# cpu_pwr.net
KiCad netlist of a schematic drawn in Altium Designer
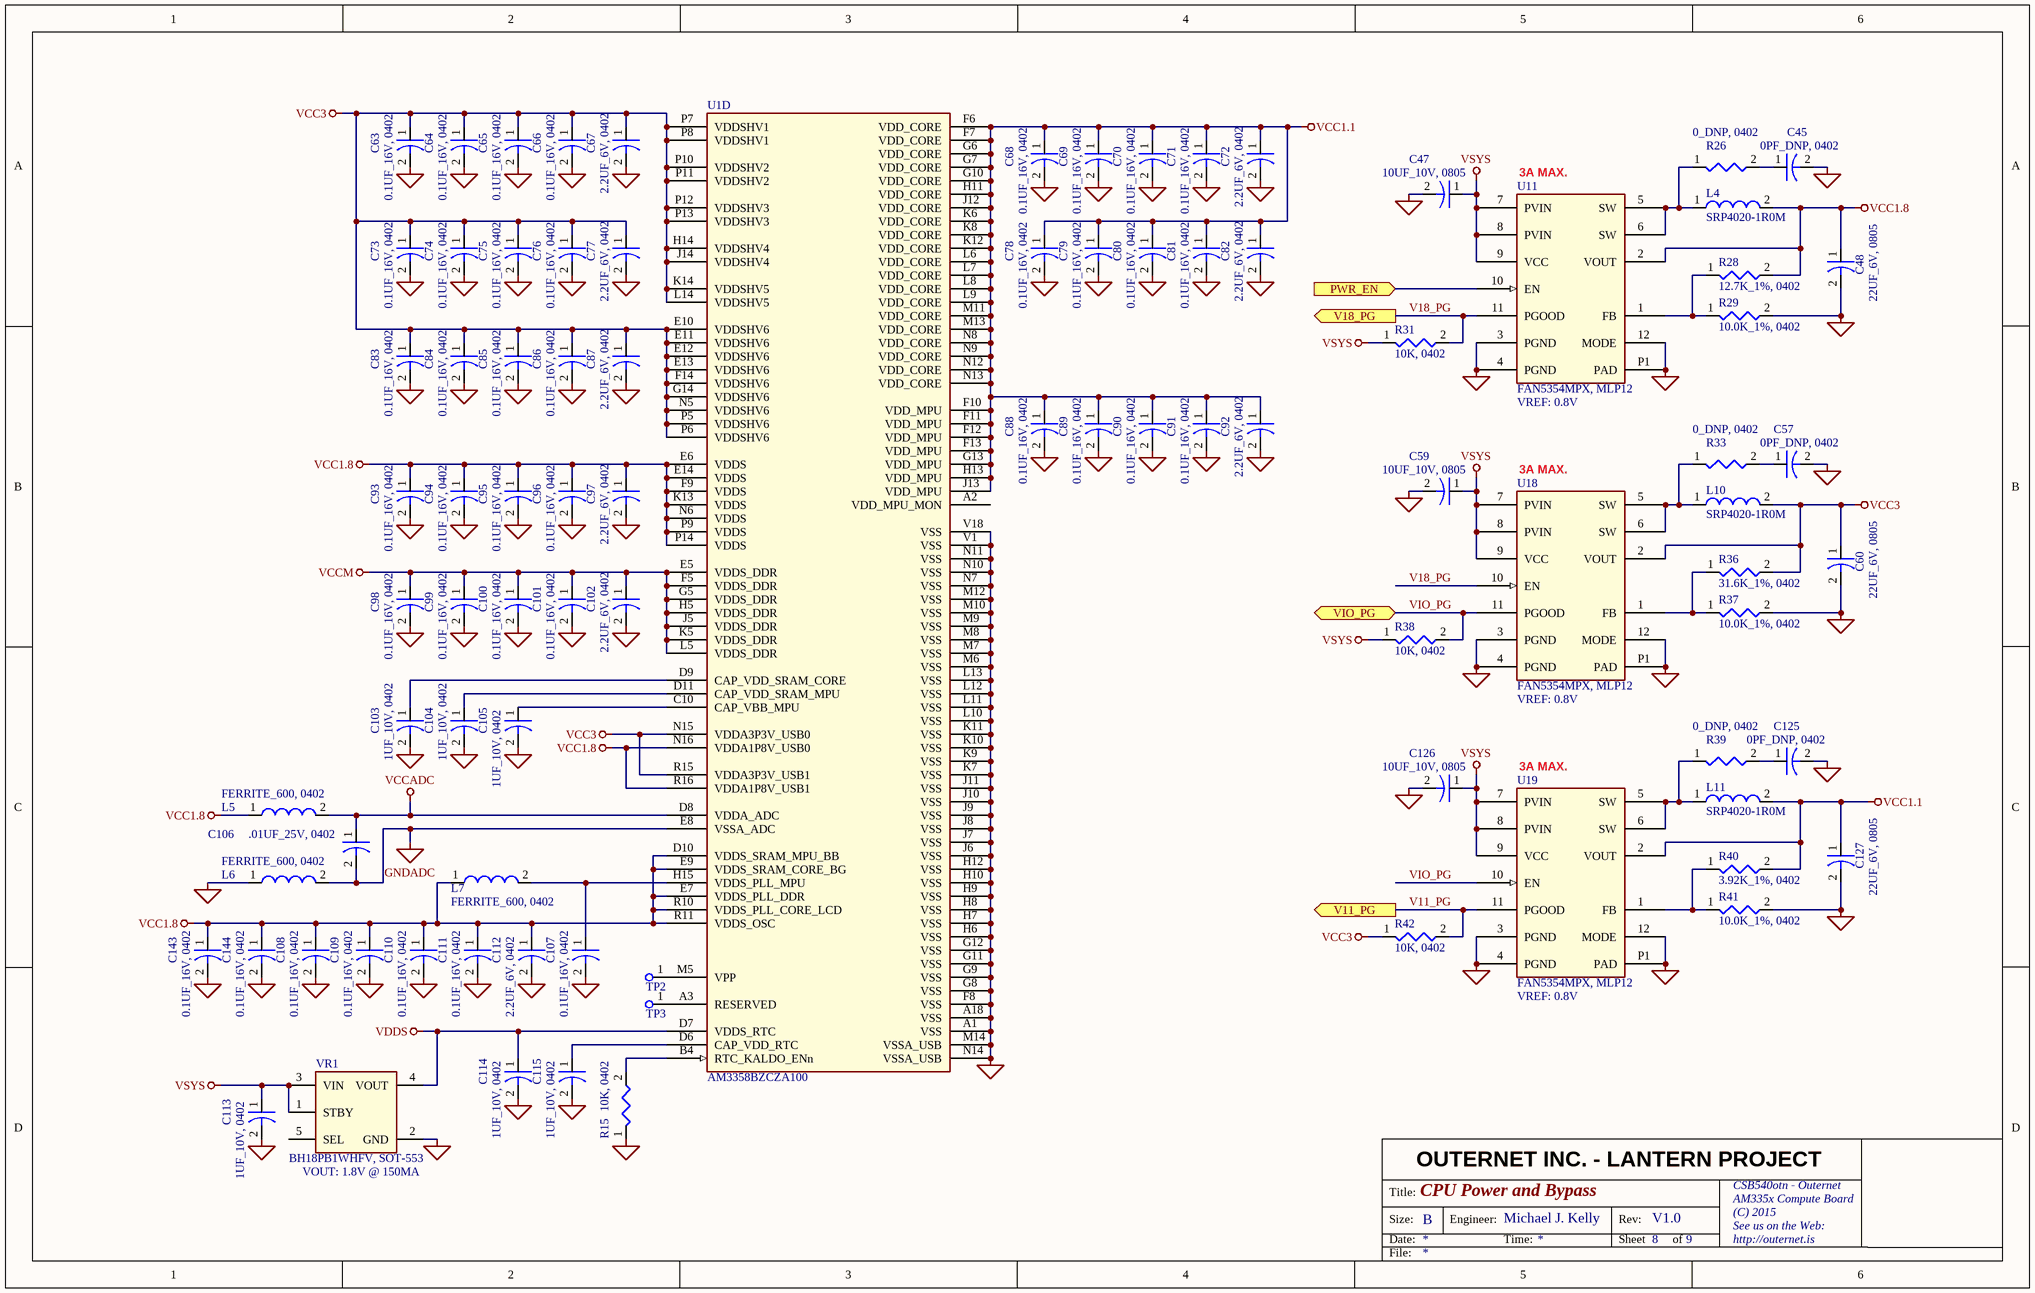
[diagram p0: cpu_pwr.SchDoc]

(export (version "E")
  (design (tool "Eeschema 10.0.6"))
  (components
    (comp (ref "C45")
      (value "0PF_DNP, 0402")
      (footprint "0402C")
      (description "CAP - 0402 PKG")
      (libsource (lib "COGENT_Library") (part "0PF_DNP, 0402"))
    )
    (comp (ref "C47")
      (value "10UF_10V, 0805")
      (footprint "0805C")
      (description "CAP - 0805 PKG")
      (libsource (lib "COGENT_Library") (part "10UF_10V, 0805"))
    )
    (comp (ref "C48")
      (value "22UF_6V, 0805")
      (footprint "0805C")
      (description "CAP - 0805 PKG")
      (libsource (lib "COGENT_Library") (part "22UF_6V, 0805"))
    )
    (comp (ref "C57")
      (value "0PF_DNP, 0402")
      (footprint "0402C")
      (description "CAP - 0402 PKG")
      (libsource (lib "COGENT_Library") (part "0PF_DNP, 0402"))
    )
    (comp (ref "C59")
      (value "10UF_10V, 0805")
      (footprint "0805C")
      (description "CAP - 0805 PKG")
      (libsource (lib "COGENT_Library") (part "10UF_10V, 0805"))
    )
    (comp (ref "C60")
      (value "22UF_6V, 0805")
      (footprint "0805C")
      (description "CAP - 0805 PKG")
      (libsource (lib "COGENT_Library") (part "22UF_6V, 0805"))
    )
    (comp (ref "C63")
      (value "0.1UF_16V, 0402")
      (footprint "0402C")
      (description "CAP - 0402 PKG")
      (libsource (lib "COGENT_Library") (part "0.1UF_16V, 0402"))
    )
    (comp (ref "C64")
      (value "0.1UF_16V, 0402")
      (footprint "0402C")
      (description "CAP - 0402 PKG")
      (libsource (lib "COGENT_Library") (part "0.1UF_16V, 0402"))
    )
    (comp (ref "C65")
      (value "0.1UF_16V, 0402")
      (footprint "0402C")
      (description "CAP - 0402 PKG")
      (libsource (lib "COGENT_Library") (part "0.1UF_16V, 0402"))
    )
    (comp (ref "C66")
      (value "0.1UF_16V, 0402")
      (footprint "0402C")
      (description "CAP - 0402 PKG")
      (libsource (lib "COGENT_Library") (part "0.1UF_16V, 0402"))
    )
    (comp (ref "C67")
      (value "2.2UF_6V, 0402")
      (footprint "0402C")
      (description "CAP - 0402 PKG")
      (libsource (lib "COGENT_Library") (part "2.2UF_6V, 0402"))
    )
    (comp (ref "C68")
      (value "0.1UF_16V, 0402")
      (footprint "0402C")
      (description "CAP - 0402 PKG")
      (libsource (lib "COGENT_Library") (part "0.1UF_16V, 0402"))
    )
    (comp (ref "C69")
      (value "0.1UF_16V, 0402")
      (footprint "0402C")
      (description "CAP - 0402 PKG")
      (libsource (lib "COGENT_Library") (part "0.1UF_16V, 0402"))
    )
    (comp (ref "C70")
      (value "0.1UF_16V, 0402")
      (footprint "0402C")
      (description "CAP - 0402 PKG")
      (libsource (lib "COGENT_Library") (part "0.1UF_16V, 0402"))
    )
    (comp (ref "C71")
      (value "0.1UF_16V, 0402")
      (footprint "0402C")
      (description "CAP - 0402 PKG")
      (libsource (lib "COGENT_Library") (part "0.1UF_16V, 0402"))
    )
    (comp (ref "C72")
      (value "2.2UF_6V, 0402")
      (footprint "0402C")
      (description "CAP - 0402 PKG")
      (libsource (lib "COGENT_Library") (part "2.2UF_6V, 0402"))
    )
    (comp (ref "C73")
      (value "0.1UF_16V, 0402")
      (footprint "0402C")
      (description "CAP - 0402 PKG")
      (libsource (lib "COGENT_Library") (part "0.1UF_16V, 0402"))
    )
    (comp (ref "C74")
      (value "0.1UF_16V, 0402")
      (footprint "0402C")
      (description "CAP - 0402 PKG")
      (libsource (lib "COGENT_Library") (part "0.1UF_16V, 0402"))
    )
    (comp (ref "C75")
      (value "0.1UF_16V, 0402")
      (footprint "0402C")
      (description "CAP - 0402 PKG")
      (libsource (lib "COGENT_Library") (part "0.1UF_16V, 0402"))
    )
    (comp (ref "C76")
      (value "0.1UF_16V, 0402")
      (footprint "0402C")
      (description "CAP - 0402 PKG")
      (libsource (lib "COGENT_Library") (part "0.1UF_16V, 0402"))
    )
    (comp (ref "C77")
      (value "2.2UF_6V, 0402")
      (footprint "0402C")
      (description "CAP - 0402 PKG")
      (libsource (lib "COGENT_Library") (part "2.2UF_6V, 0402"))
    )
    (comp (ref "C78")
      (value "0.1UF_16V, 0402")
      (footprint "0402C")
      (description "CAP - 0402 PKG")
      (libsource (lib "COGENT_Library") (part "0.1UF_16V, 0402"))
    )
    (comp (ref "C79")
      (value "0.1UF_16V, 0402")
      (footprint "0402C")
      (description "CAP - 0402 PKG")
      (libsource (lib "COGENT_Library") (part "0.1UF_16V, 0402"))
    )
    (comp (ref "C80")
      (value "0.1UF_16V, 0402")
      (footprint "0402C")
      (description "CAP - 0402 PKG")
      (libsource (lib "COGENT_Library") (part "0.1UF_16V, 0402"))
    )
    (comp (ref "C81")
      (value "0.1UF_16V, 0402")
      (footprint "0402C")
      (description "CAP - 0402 PKG")
      (libsource (lib "COGENT_Library") (part "0.1UF_16V, 0402"))
    )
    (comp (ref "C82")
      (value "2.2UF_6V, 0402")
      (footprint "0402C")
      (description "CAP - 0402 PKG")
      (libsource (lib "COGENT_Library") (part "2.2UF_6V, 0402"))
    )
    (comp (ref "C83")
      (value "0.1UF_16V, 0402")
      (footprint "0402C")
      (description "CAP - 0402 PKG")
      (libsource (lib "COGENT_Library") (part "0.1UF_16V, 0402"))
    )
    (comp (ref "C84")
      (value "0.1UF_16V, 0402")
      (footprint "0402C")
      (description "CAP - 0402 PKG")
      (libsource (lib "COGENT_Library") (part "0.1UF_16V, 0402"))
    )
    (comp (ref "C85")
      (value "0.1UF_16V, 0402")
      (footprint "0402C")
      (description "CAP - 0402 PKG")
      (libsource (lib "COGENT_Library") (part "0.1UF_16V, 0402"))
    )
    (comp (ref "C86")
      (value "0.1UF_16V, 0402")
      (footprint "0402C")
      (description "CAP - 0402 PKG")
      (libsource (lib "COGENT_Library") (part "0.1UF_16V, 0402"))
    )
    (comp (ref "C87")
      (value "2.2UF_6V, 0402")
      (footprint "0402C")
      (description "CAP - 0402 PKG")
      (libsource (lib "COGENT_Library") (part "2.2UF_6V, 0402"))
    )
    (comp (ref "C88")
      (value "0.1UF_16V, 0402")
      (footprint "0402C")
      (description "CAP - 0402 PKG")
      (libsource (lib "COGENT_Library") (part "0.1UF_16V, 0402"))
    )
    (comp (ref "C89")
      (value "0.1UF_16V, 0402")
      (footprint "0402C")
      (description "CAP - 0402 PKG")
      (libsource (lib "COGENT_Library") (part "0.1UF_16V, 0402"))
    )
    (comp (ref "C90")
      (value "0.1UF_16V, 0402")
      (footprint "0402C")
      (description "CAP - 0402 PKG")
      (libsource (lib "COGENT_Library") (part "0.1UF_16V, 0402"))
    )
    (comp (ref "C91")
      (value "0.1UF_16V, 0402")
      (footprint "0402C")
      (description "CAP - 0402 PKG")
      (libsource (lib "COGENT_Library") (part "0.1UF_16V, 0402"))
    )
    (comp (ref "C92")
      (value "2.2UF_6V, 0402")
      (footprint "0402C")
      (description "CAP - 0402 PKG")
      (libsource (lib "COGENT_Library") (part "2.2UF_6V, 0402"))
    )
    (comp (ref "C93")
      (value "0.1UF_16V, 0402")
      (footprint "0402C")
      (description "CAP - 0402 PKG")
      (libsource (lib "COGENT_Library") (part "0.1UF_16V, 0402"))
    )
    (comp (ref "C94")
      (value "0.1UF_16V, 0402")
      (footprint "0402C")
      (description "CAP - 0402 PKG")
      (libsource (lib "COGENT_Library") (part "0.1UF_16V, 0402"))
    )
    (comp (ref "C95")
      (value "0.1UF_16V, 0402")
      (footprint "0402C")
      (description "CAP - 0402 PKG")
      (libsource (lib "COGENT_Library") (part "0.1UF_16V, 0402"))
    )
    (comp (ref "C96")
      (value "0.1UF_16V, 0402")
      (footprint "0402C")
      (description "CAP - 0402 PKG")
      (libsource (lib "COGENT_Library") (part "0.1UF_16V, 0402"))
    )
    (comp (ref "C97")
      (value "2.2UF_6V, 0402")
      (footprint "0402C")
      (description "CAP - 0402 PKG")
      (libsource (lib "COGENT_Library") (part "2.2UF_6V, 0402"))
    )
    (comp (ref "C98")
      (value "0.1UF_16V, 0402")
      (footprint "0402C")
      (description "CAP - 0402 PKG")
      (libsource (lib "COGENT_Library") (part "0.1UF_16V, 0402"))
    )
    (comp (ref "C99")
      (value "0.1UF_16V, 0402")
      (footprint "0402C")
      (description "CAP - 0402 PKG")
      (libsource (lib "COGENT_Library") (part "0.1UF_16V, 0402"))
    )
    (comp (ref "C100")
      (value "0.1UF_16V, 0402")
      (footprint "0402C")
      (description "CAP - 0402 PKG")
      (libsource (lib "COGENT_Library") (part "0.1UF_16V, 0402"))
    )
    (comp (ref "C101")
      (value "0.1UF_16V, 0402")
      (footprint "0402C")
      (description "CAP - 0402 PKG")
      (libsource (lib "COGENT_Library") (part "0.1UF_16V, 0402"))
    )
    (comp (ref "C102")
      (value "2.2UF_6V, 0402")
      (footprint "0402C")
      (description "CAP - 0402 PKG")
      (libsource (lib "COGENT_Library") (part "2.2UF_6V, 0402"))
    )
    (comp (ref "C103")
      (value "1UF_10V, 0402")
      (footprint "0402C")
      (description "CAP - 0402 PKG")
      (libsource (lib "COGENT_Library") (part "1UF_10V, 0402"))
    )
    (comp (ref "C104")
      (value "1UF_10V, 0402")
      (footprint "0402C")
      (description "CAP - 0402 PKG")
      (libsource (lib "COGENT_Library") (part "1UF_10V, 0402"))
    )
    (comp (ref "C105")
      (value "1UF_10V, 0402")
      (footprint "0402C")
      (description "CAP - 0402 PKG")
      (libsource (lib "COGENT_Library") (part "1UF_10V, 0402"))
    )
    (comp (ref "C106")
      (value ".01UF_25V, 0402")
      (footprint "0402C")
      (description "CAP - 0402 PKG")
      (libsource (lib "COGENT_Library") (part ".01UF_25V, 0402"))
    )
    (comp (ref "C107")
      (value "0.1UF_16V, 0402")
      (footprint "0402C")
      (description "CAP - 0402 PKG")
      (libsource (lib "COGENT_Library") (part "0.1UF_16V, 0402"))
    )
    (comp (ref "C108")
      (value "0.1UF_16V, 0402")
      (footprint "0402C")
      (description "CAP - 0402 PKG")
      (libsource (lib "COGENT_Library") (part "0.1UF_16V, 0402"))
    )
    (comp (ref "C109")
      (value "0.1UF_16V, 0402")
      (footprint "0402C")
      (description "CAP - 0402 PKG")
      (libsource (lib "COGENT_Library") (part "0.1UF_16V, 0402"))
    )
    (comp (ref "C110")
      (value "0.1UF_16V, 0402")
      (footprint "0402C")
      (description "CAP - 0402 PKG")
      (libsource (lib "COGENT_Library") (part "0.1UF_16V, 0402"))
    )
    (comp (ref "C111")
      (value "0.1UF_16V, 0402")
      (footprint "0402C")
      (description "CAP - 0402 PKG")
      (libsource (lib "COGENT_Library") (part "0.1UF_16V, 0402"))
    )
    (comp (ref "C112")
      (value "2.2UF_6V, 0402")
      (footprint "0402C")
      (description "CAP - 0402 PKG")
      (libsource (lib "COGENT_Library") (part "2.2UF_6V, 0402"))
    )
    (comp (ref "C113")
      (value "1UF_10V, 0402")
      (footprint "0402C")
      (description "CAP - 0402 PKG")
      (libsource (lib "COGENT_Library") (part "1UF_10V, 0402"))
    )
    (comp (ref "C114")
      (value "1UF_10V, 0402")
      (footprint "0402C")
      (description "CAP - 0402 PKG")
      (libsource (lib "COGENT_Library") (part "1UF_10V, 0402"))
    )
    (comp (ref "C115")
      (value "1UF_10V, 0402")
      (footprint "0402C")
      (description "CAP - 0402 PKG")
      (libsource (lib "COGENT_Library") (part "1UF_10V, 0402"))
    )
    (comp (ref "C125")
      (value "0PF_DNP, 0402")
      (footprint "0402C")
      (description "CAP - 0402 PKG")
      (libsource (lib "COGENT_Library") (part "0PF_DNP, 0402"))
    )
    (comp (ref "C126")
      (value "10UF_10V, 0805")
      (footprint "0805C")
      (description "CAP - 0805 PKG")
      (libsource (lib "COGENT_Library") (part "10UF_10V, 0805"))
    )
    (comp (ref "C127")
      (value "22UF_6V, 0805")
      (footprint "0805C")
      (description "CAP - 0805 PKG")
      (libsource (lib "COGENT_Library") (part "22UF_6V, 0805"))
    )
    (comp (ref "C143")
      (value "0.1UF_16V, 0402")
      (footprint "0402C")
      (description "CAP - 0402 PKG")
      (libsource (lib "COGENT_Library") (part "0.1UF_16V, 0402"))
    )
    (comp (ref "C144")
      (value "0.1UF_16V, 0402")
      (footprint "0402C")
      (description "CAP - 0402 PKG")
      (libsource (lib "COGENT_Library") (part "0.1UF_16V, 0402"))
    )
    (comp (ref "L4")
      (value "SRP4020-1R0M")
      (footprint "SRP4020")
      (description "INDUCTOR - 1.0UH, 5/6A, 4MM x 4MM x 2MM, 22mohm")
      (libsource (lib "COGENT_Library") (part "SRP4020-1R0M"))
    )
    (comp (ref "L5")
      (value "FERRITE_600, 0402")
      (footprint "0402L")
      (description "FERRITE BEAD - 600 OHM, 300MA, 0402 PKG")
      (libsource (lib "COGENT_Library") (part "FERRITE_600, 0402"))
    )
    (comp (ref "L6")
      (value "FERRITE_600, 0402")
      (footprint "0402L")
      (description "FERRITE BEAD - 600 OHM, 300MA, 0402 PKG")
      (libsource (lib "COGENT_Library") (part "FERRITE_600, 0402"))
    )
    (comp (ref "L7")
      (value "FERRITE_600, 0402")
      (footprint "0402L")
      (description "FERRITE BEAD - 600 OHM, 300MA, 0402 PKG")
      (libsource (lib "COGENT_Library") (part "FERRITE_600, 0402"))
    )
    (comp (ref "L10")
      (value "SRP4020-1R0M")
      (footprint "SRP4020")
      (description "INDUCTOR - 1.0UH, 5/6A, 4MM x 4MM x 2MM, 22mohm")
      (libsource (lib "COGENT_Library") (part "SRP4020-1R0M"))
    )
    (comp (ref "L11")
      (value "SRP4020-1R0M")
      (footprint "SRP4020")
      (description "INDUCTOR - 1.0UH, 5/6A, 4MM x 4MM x 2MM, 22mohm")
      (libsource (lib "COGENT_Library") (part "SRP4020-1R0M"))
    )
    (comp (ref "R15")
      (value "10K, 0402")
      (footprint "0402R")
      (description "RES - 0402 PKG")
      (libsource (lib "COGENT_Library") (part "10K, 0402"))
    )
    (comp (ref "R26")
      (value "0_DNP, 0402")
      (footprint "0402R")
      (description "RES - 0402 PKG, DO NOT POPULATE BY DEFAULT")
      (libsource (lib "COGENT_Library") (part "0_DNP, 0402"))
    )
    (comp (ref "R28")
      (value "12.7K_1%, 0402")
      (footprint "0402R")
      (description "RES - 0402 PKG")
      (libsource (lib "COGENT_Library") (part "12.7K_1%, 0402"))
    )
    (comp (ref "R29")
      (value "10.0K_1%, 0402")
      (footprint "0402R")
      (description "RES - 0402 PKG")
      (libsource (lib "COGENT_Library") (part "10.0K_1%, 0402"))
    )
    (comp (ref "R31")
      (value "10K, 0402")
      (footprint "0402R")
      (description "RES - 0402 PKG")
      (libsource (lib "COGENT_Library") (part "10K, 0402"))
    )
    (comp (ref "R33")
      (value "0_DNP, 0402")
      (footprint "0402R")
      (description "RES - 0402 PKG, DO NOT POPULATE BY DEFAULT")
      (libsource (lib "COGENT_Library") (part "0_DNP, 0402"))
    )
    (comp (ref "R36")
      (value "31.6K_1%, 0402")
      (footprint "0402R")
      (description "RES - 0402 PKG")
      (libsource (lib "COGENT_Library") (part "31.6K_1%, 0402"))
    )
    (comp (ref "R37")
      (value "10.0K_1%, 0402")
      (footprint "0402R")
      (description "RES - 0402 PKG")
      (libsource (lib "COGENT_Library") (part "10.0K_1%, 0402"))
    )
    (comp (ref "R38")
      (value "10K, 0402")
      (footprint "0402R")
      (description "RES - 0402 PKG")
      (libsource (lib "COGENT_Library") (part "10K, 0402"))
    )
    (comp (ref "R39")
      (value "0_DNP, 0402")
      (footprint "0402R")
      (description "RES - 0402 PKG, DO NOT POPULATE BY DEFAULT")
      (libsource (lib "COGENT_Library") (part "0_DNP, 0402"))
    )
    (comp (ref "R40")
      (value "3.92K_1%, 0402")
      (footprint "0402R")
      (description "RES - 0402 PKG")
      (libsource (lib "COGENT_Library") (part "3.92K_1%, 0402"))
    )
    (comp (ref "R41")
      (value "10.0K_1%, 0402")
      (footprint "0402R")
      (description "RES - 0402 PKG")
      (libsource (lib "COGENT_Library") (part "10.0K_1%, 0402"))
    )
    (comp (ref "R42")
      (value "10K, 0402")
      (footprint "0402R")
      (description "RES - 0402 PKG")
      (libsource (lib "COGENT_Library") (part "10K, 0402"))
    )
    (comp (ref "TP2")
      (value "TP20R")
      (footprint "TP_20R")
      (description "MISC - TEST PAD, 20MIL ROUND")
      (libsource (lib "COGENT_Library") (part "TP20R"))
    )
    (comp (ref "TP3")
      (value "TP20R")
      (footprint "TP_20R")
      (description "MISC - TEST PAD, 20MIL ROUND")
      (libsource (lib "COGENT_Library") (part "TP20R"))
    )
    (comp (ref "U1")
      (value "AM3358BZCZA100")
      (footprint "BGA324x18")
      (description "MPU - CORTEX-A8 CORE, SDIO, GIGe, USB x2, UART x3, CAN, 2D/3D")
      (libsource (lib "COGENT_Library") (part "AM3358BZCZA100"))
    )
    (comp (ref "U11")
      (value "FAN5354MPX, MLP12")
      (footprint "mlp12")
      (description "SWITCHER - 270ua Iq, 3A, 2.7V TO 5.5V IN, 0.8V TO VIN OUT")
      (fields (field (name "VREF") "0.8V"))
      (libsource (lib "COGENT_Library") (part "FAN5354MPX, MLP12"))
    )
    (comp (ref "U18")
      (value "FAN5354MPX, MLP12")
      (footprint "mlp12")
      (description "SWITCHER - 270ua Iq, 3A, 2.7V TO 5.5V IN, 0.8V TO VIN OUT")
      (fields (field (name "VREF") "0.8V"))
      (libsource (lib "COGENT_Library") (part "FAN5354MPX, MLP12"))
    )
    (comp (ref "U19")
      (value "FAN5354MPX, MLP12")
      (footprint "mlp12")
      (description "SWITCHER - 270ua Iq, 3A, 2.7V TO 5.5V IN, 0.8V TO VIN OUT")
      (fields (field (name "VREF") "0.8V"))
      (libsource (lib "COGENT_Library") (part "FAN5354MPX, MLP12"))
    )
    (comp (ref "VR1")
      (value "BH18PB1WHFV, SOT-553")
      (footprint "SOT-553")
      (description "LDO - 4ua Iq, 150ma, 3.4V - 5.5V IN, 1.8V OUT, 600mv Vdrop")
      (fields (field (name "VOUT") "1.8V @ 150MA"))
      (libsource (lib "COGENT_Library") (part "BH18PB1WHFV, SOT-553"))
    )
  )
  (nets
    (net (code "1") (name "/PWR_EN") (class "Default")
      (node (ref "U11") (pin "10") (pinfunction "EN_10") (pintype "input"))
    )
    (net (code "2") (name "/V11_PG") (class "Default")
      (node (ref "R42") (pin "2") (pinfunction "2_2") (pintype "passive"))
      (node (ref "U19") (pin "11") (pinfunction "PGOOD_11") (pintype "open_collector"))
    )
    (net (code "3") (name "/V18_PG") (class "Default")
      (node (ref "R31") (pin "2") (pinfunction "2_2") (pintype "passive"))
      (node (ref "U11") (pin "11") (pinfunction "PGOOD_11") (pintype "open_collector"))
      (node (ref "U18") (pin "10") (pinfunction "EN_10") (pintype "input"))
    )
    (net (code "4") (name "/VIO_PG") (class "Default")
      (node (ref "R38") (pin "2") (pinfunction "2_2") (pintype "passive"))
      (node (ref "U18") (pin "11") (pinfunction "PGOOD_11") (pintype "open_collector"))
      (node (ref "U19") (pin "10") (pinfunction "EN_10") (pintype "input"))
    )
    (net (code "5") (name "GND") (class "Default")
      (node (ref "C100") (pin "2") (pinfunction "2_2") (pintype "passive"))
      (node (ref "C101") (pin "2") (pinfunction "2_2") (pintype "passive"))
      (node (ref "C102") (pin "2") (pinfunction "2_2") (pintype "passive"))
      (node (ref "C103") (pin "2") (pinfunction "2_2") (pintype "passive"))
      (node (ref "C104") (pin "2") (pinfunction "2_2") (pintype "passive"))
      (node (ref "C105") (pin "2") (pinfunction "2_2") (pintype "passive"))
      (node (ref "C107") (pin "2") (pinfunction "2_2") (pintype "passive"))
      (node (ref "C108") (pin "2") (pinfunction "2_2") (pintype "passive"))
      (node (ref "C109") (pin "2") (pinfunction "2_2") (pintype "passive"))
      (node (ref "C110") (pin "2") (pinfunction "2_2") (pintype "passive"))
      (node (ref "C111") (pin "2") (pinfunction "2_2") (pintype "passive"))
      (node (ref "C112") (pin "2") (pinfunction "2_2") (pintype "passive"))
      (node (ref "C113") (pin "2") (pinfunction "2_2") (pintype "passive"))
      (node (ref "C114") (pin "2") (pinfunction "2_2") (pintype "passive"))
      (node (ref "C115") (pin "2") (pinfunction "2_2") (pintype "passive"))
      (node (ref "C125") (pin "2") (pinfunction "2_2") (pintype "passive"))
      (node (ref "C126") (pin "2") (pinfunction "2_2") (pintype "passive"))
      (node (ref "C127") (pin "2") (pinfunction "2_2") (pintype "passive"))
      (node (ref "C143") (pin "2") (pinfunction "2_2") (pintype "passive"))
      (node (ref "C144") (pin "2") (pinfunction "2_2") (pintype "passive"))
      (node (ref "C45") (pin "2") (pinfunction "2_2") (pintype "passive"))
      (node (ref "C47") (pin "2") (pinfunction "2_2") (pintype "passive"))
      (node (ref "C48") (pin "2") (pinfunction "2_2") (pintype "passive"))
      (node (ref "C57") (pin "2") (pinfunction "2_2") (pintype "passive"))
      (node (ref "C59") (pin "2") (pinfunction "2_2") (pintype "passive"))
      (node (ref "C60") (pin "2") (pinfunction "2_2") (pintype "passive"))
      (node (ref "C63") (pin "2") (pinfunction "2_2") (pintype "passive"))
      (node (ref "C64") (pin "2") (pinfunction "2_2") (pintype "passive"))
      (node (ref "C65") (pin "2") (pinfunction "2_2") (pintype "passive"))
      (node (ref "C66") (pin "2") (pinfunction "2_2") (pintype "passive"))
      (node (ref "C67") (pin "2") (pinfunction "2_2") (pintype "passive"))
      (node (ref "C68") (pin "2") (pinfunction "2_2") (pintype "passive"))
      (node (ref "C69") (pin "2") (pinfunction "2_2") (pintype "passive"))
      (node (ref "C70") (pin "2") (pinfunction "2_2") (pintype "passive"))
      (node (ref "C71") (pin "2") (pinfunction "2_2") (pintype "passive"))
      (node (ref "C72") (pin "2") (pinfunction "2_2") (pintype "passive"))
      (node (ref "C73") (pin "2") (pinfunction "2_2") (pintype "passive"))
      (node (ref "C74") (pin "2") (pinfunction "2_2") (pintype "passive"))
      (node (ref "C75") (pin "2") (pinfunction "2_2") (pintype "passive"))
      (node (ref "C76") (pin "2") (pinfunction "2_2") (pintype "passive"))
      (node (ref "C77") (pin "2") (pinfunction "2_2") (pintype "passive"))
      (node (ref "C78") (pin "2") (pinfunction "2_2") (pintype "passive"))
      (node (ref "C79") (pin "2") (pinfunction "2_2") (pintype "passive"))
      (node (ref "C80") (pin "2") (pinfunction "2_2") (pintype "passive"))
      (node (ref "C81") (pin "2") (pinfunction "2_2") (pintype "passive"))
      (node (ref "C82") (pin "2") (pinfunction "2_2") (pintype "passive"))
      (node (ref "C83") (pin "2") (pinfunction "2_2") (pintype "passive"))
      (node (ref "C84") (pin "2") (pinfunction "2_2") (pintype "passive"))
      (node (ref "C85") (pin "2") (pinfunction "2_2") (pintype "passive"))
      (node (ref "C86") (pin "2") (pinfunction "2_2") (pintype "passive"))
      (node (ref "C87") (pin "2") (pinfunction "2_2") (pintype "passive"))
      (node (ref "C88") (pin "2") (pinfunction "2_2") (pintype "passive"))
      (node (ref "C89") (pin "2") (pinfunction "2_2") (pintype "passive"))
      (node (ref "C90") (pin "2") (pinfunction "2_2") (pintype "passive"))
      (node (ref "C91") (pin "2") (pinfunction "2_2") (pintype "passive"))
      (node (ref "C92") (pin "2") (pinfunction "2_2") (pintype "passive"))
      (node (ref "C93") (pin "2") (pinfunction "2_2") (pintype "passive"))
      (node (ref "C94") (pin "2") (pinfunction "2_2") (pintype "passive"))
      (node (ref "C95") (pin "2") (pinfunction "2_2") (pintype "passive"))
      (node (ref "C96") (pin "2") (pinfunction "2_2") (pintype "passive"))
      (node (ref "C97") (pin "2") (pinfunction "2_2") (pintype "passive"))
      (node (ref "C98") (pin "2") (pinfunction "2_2") (pintype "passive"))
      (node (ref "C99") (pin "2") (pinfunction "2_2") (pintype "passive"))
      (node (ref "L6") (pin "1") (pinfunction "1_1") (pintype "passive"))
      (node (ref "R15") (pin "1") (pinfunction "1_1") (pintype "passive"))
      (node (ref "R29") (pin "2") (pinfunction "2_2") (pintype "passive"))
      (node (ref "R37") (pin "2") (pinfunction "2_2") (pintype "passive"))
      (node (ref "R41") (pin "2") (pinfunction "2_2") (pintype "passive"))
      (node (ref "U1") (pin "A1") (pinfunction "VSS_A1") (pintype "power_in"))
      (node (ref "U1") (pin "A18") (pinfunction "VSS_A18") (pintype "power_in"))
      (node (ref "U1") (pin "F8") (pinfunction "VSS_F8") (pintype "power_in"))
      (node (ref "U1") (pin "G11") (pinfunction "VSS_G11") (pintype "power_in"))
      (node (ref "U1") (pin "G12") (pinfunction "VSS_G12") (pintype "power_in"))
      (node (ref "U1") (pin "G8") (pinfunction "VSS_G8") (pintype "power_in"))
      (node (ref "U1") (pin "G9") (pinfunction "VSS_G9") (pintype "power_in"))
      (node (ref "U1") (pin "H10") (pinfunction "VSS_H10") (pintype "power_in"))
      (node (ref "U1") (pin "H12") (pinfunction "VSS_H12") (pintype "power_in"))
      (node (ref "U1") (pin "H6") (pinfunction "VSS_H6") (pintype "power_in"))
      (node (ref "U1") (pin "H7") (pinfunction "VSS_H7") (pintype "power_in"))
      (node (ref "U1") (pin "H8") (pinfunction "VSS_H8") (pintype "power_in"))
      (node (ref "U1") (pin "H9") (pinfunction "VSS_H9") (pintype "power_in"))
      (node (ref "U1") (pin "J10") (pinfunction "VSS_J10") (pintype "power_in"))
      (node (ref "U1") (pin "J11") (pinfunction "VSS_J11") (pintype "power_in"))
      (node (ref "U1") (pin "J6") (pinfunction "VSS_J6") (pintype "power_in"))
      (node (ref "U1") (pin "J7") (pinfunction "VSS_J7") (pintype "power_in"))
      (node (ref "U1") (pin "J8") (pinfunction "VSS_J8") (pintype "power_in"))
      (node (ref "U1") (pin "J9") (pinfunction "VSS_J9") (pintype "power_in"))
      (node (ref "U1") (pin "K10") (pinfunction "VSS_K10") (pintype "power_in"))
      (node (ref "U1") (pin "K11") (pinfunction "VSS_K11") (pintype "power_in"))
      (node (ref "U1") (pin "K7") (pinfunction "VSS_K7") (pintype "power_in"))
      (node (ref "U1") (pin "K9") (pinfunction "VSS_K9") (pintype "power_in"))
      (node (ref "U1") (pin "L10") (pinfunction "VSS_L10") (pintype "power_in"))
      (node (ref "U1") (pin "L11") (pinfunction "VSS_L11") (pintype "power_in"))
      (node (ref "U1") (pin "L12") (pinfunction "VSS_L12") (pintype "power_in"))
      (node (ref "U1") (pin "L13") (pinfunction "VSS_L13") (pintype "power_in"))
      (node (ref "U1") (pin "M10") (pinfunction "VSS_M10") (pintype "power_in"))
      (node (ref "U1") (pin "M12") (pinfunction "VSS_M12") (pintype "power_in"))
      (node (ref "U1") (pin "M14") (pinfunction "VSSA_USB_M14") (pintype "power_in"))
      (node (ref "U1") (pin "M6") (pinfunction "VSS_M6") (pintype "power_in"))
      (node (ref "U1") (pin "M7") (pinfunction "VSS_M7") (pintype "power_in"))
      (node (ref "U1") (pin "M8") (pinfunction "VSS_M8") (pintype "power_in"))
      (node (ref "U1") (pin "M9") (pinfunction "VSS_M9") (pintype "power_in"))
      (node (ref "U1") (pin "N10") (pinfunction "VSS_N10") (pintype "power_in"))
      (node (ref "U1") (pin "N11") (pinfunction "VSS_N11") (pintype "power_in"))
      (node (ref "U1") (pin "N14") (pinfunction "VSSA_USB_N14") (pintype "power_in"))
      (node (ref "U1") (pin "N7") (pinfunction "VSS_N7") (pintype "power_in"))
      (node (ref "U1") (pin "V1") (pinfunction "VSS_V1") (pintype "power_in"))
      (node (ref "U1") (pin "V18") (pinfunction "VSS_V18") (pintype "power_in"))
      (node (ref "U11") (pin "12") (pinfunction "MODE_12") (pintype "passive"))
      (node (ref "U11") (pin "3") (pinfunction "PGND_3") (pintype "power_in"))
      (node (ref "U11") (pin "4") (pinfunction "PGND_4") (pintype "power_in"))
      (node (ref "U11") (pin "P1") (pinfunction "PAD_P1") (pintype "power_in"))
      (node (ref "U18") (pin "12") (pinfunction "MODE_12") (pintype "passive"))
      (node (ref "U18") (pin "3") (pinfunction "PGND_3") (pintype "power_in"))
      (node (ref "U18") (pin "4") (pinfunction "PGND_4") (pintype "power_in"))
      (node (ref "U18") (pin "P1") (pinfunction "PAD_P1") (pintype "power_in"))
      (node (ref "U19") (pin "12") (pinfunction "MODE_12") (pintype "passive"))
      (node (ref "U19") (pin "3") (pinfunction "PGND_3") (pintype "power_in"))
      (node (ref "U19") (pin "4") (pinfunction "PGND_4") (pintype "power_in"))
      (node (ref "U19") (pin "P1") (pinfunction "PAD_P1") (pintype "power_in"))
      (node (ref "VR1") (pin "2") (pinfunction "GND_2") (pintype "passive"))
    )
    (net (code "6") (name "GNDADC") (class "Default")
      (node (ref "C106") (pin "2") (pinfunction "2_2") (pintype "passive"))
      (node (ref "L6") (pin "2") (pinfunction "2_2") (pintype "passive"))
      (node (ref "U1") (pin "E8") (pinfunction "VSSA_ADC_E8") (pintype "power_in"))
    )
    (net (code "7") (name "Net-(C45-Pad1)") (class "Default")
      (node (ref "C45") (pin "1") (pinfunction "1_1") (pintype "passive"))
      (node (ref "R26") (pin "2") (pinfunction "2_2") (pintype "passive"))
    )
    (net (code "8") (name "Net-(C57-Pad1)") (class "Default")
      (node (ref "C57") (pin "1") (pinfunction "1_1") (pintype "passive"))
      (node (ref "R33") (pin "2") (pinfunction "2_2") (pintype "passive"))
    )
    (net (code "9") (name "Net-(C125-Pad1)") (class "Default")
      (node (ref "C125") (pin "1") (pinfunction "1_1") (pintype "passive"))
      (node (ref "R39") (pin "2") (pinfunction "2_2") (pintype "passive"))
    )
    (net (code "10") (name "Net-(L4-Pad1)") (class "Default")
      (node (ref "L4") (pin "1") (pinfunction "1_1") (pintype "passive"))
      (node (ref "R26") (pin "1") (pinfunction "1_1") (pintype "passive"))
      (node (ref "U11") (pin "5") (pinfunction "SW_5") (pintype "passive"))
      (node (ref "U11") (pin "6") (pinfunction "SW_6") (pintype "passive"))
    )
    (net (code "11") (name "Net-(L10-Pad1)") (class "Default")
      (node (ref "L10") (pin "1") (pinfunction "1_1") (pintype "passive"))
      (node (ref "R33") (pin "1") (pinfunction "1_1") (pintype "passive"))
      (node (ref "U18") (pin "5") (pinfunction "SW_5") (pintype "passive"))
      (node (ref "U18") (pin "6") (pinfunction "SW_6") (pintype "passive"))
    )
    (net (code "12") (name "Net-(L11-Pad1)") (class "Default")
      (node (ref "L11") (pin "1") (pinfunction "1_1") (pintype "passive"))
      (node (ref "R39") (pin "1") (pinfunction "1_1") (pintype "passive"))
      (node (ref "U19") (pin "5") (pinfunction "SW_5") (pintype "passive"))
      (node (ref "U19") (pin "6") (pinfunction "SW_6") (pintype "passive"))
    )
    (net (code "13") (name "Net-(TP2-TP)") (class "Default")
      (node (ref "TP2") (pin "1") (pinfunction "TP_1") (pintype "passive"))
      (node (ref "U1") (pin "M5") (pinfunction "VPP_M5") (pintype "power_in"))
    )
    (net (code "14") (name "Net-(TP3-TP)") (class "Default")
      (node (ref "TP3") (pin "1") (pinfunction "TP_1") (pintype "passive"))
      (node (ref "U1") (pin "A3") (pinfunction "RESERVED_A3") (pintype "passive"))
    )
    (net (code "15") (name "Net-(U1D-CAP_VBB_MPU)") (class "Default")
      (node (ref "C105") (pin "1") (pinfunction "1_1") (pintype "passive"))
      (node (ref "U1") (pin "C10") (pinfunction "CAP_VBB_MPU_C10") (pintype "passive"))
    )
    (net (code "16") (name "Net-(U1D-CAP_VDD_RTC)") (class "Default")
      (node (ref "C115") (pin "1") (pinfunction "1_1") (pintype "passive"))
      (node (ref "U1") (pin "D6") (pinfunction "CAP_VDD_RTC_D6") (pintype "power_in"))
    )
    (net (code "17") (name "Net-(U1D-CAP_VDD_SRAM_CORE)") (class "Default")
      (node (ref "C103") (pin "1") (pinfunction "1_1") (pintype "passive"))
      (node (ref "U1") (pin "D9") (pinfunction "CAP_VDD_SRAM_CORE_D9") (pintype "power_in"))
    )
    (net (code "18") (name "Net-(U1D-CAP_VDD_SRAM_MPU)") (class "Default")
      (node (ref "C104") (pin "1") (pinfunction "1_1") (pintype "passive"))
      (node (ref "U1") (pin "D11") (pinfunction "CAP_VDD_SRAM_MPU_D11") (pintype "power_in"))
    )
    (net (code "19") (name "Net-(U1D-RTC_KALDO_ENn)") (class "Default")
      (node (ref "R15") (pin "2") (pinfunction "2_2") (pintype "passive"))
      (node (ref "U1") (pin "B4") (pinfunction "RTC_KALDO_ENn_B4") (pintype "input"))
    )
    (net (code "20") (name "Net-(U1D-VDDS_PLL_MPU)") (class "Default")
      (node (ref "C107") (pin "1") (pinfunction "1_1") (pintype "passive"))
      (node (ref "L7") (pin "2") (pinfunction "2_2") (pintype "passive"))
      (node (ref "U1") (pin "H15") (pinfunction "VDDS_PLL_MPU_H15") (pintype "power_in"))
    )
    (net (code "21") (name "Net-(U11-FB)") (class "Default")
      (node (ref "R28") (pin "1") (pinfunction "1_1") (pintype "passive"))
      (node (ref "R29") (pin "1") (pinfunction "1_1") (pintype "passive"))
      (node (ref "U11") (pin "1") (pinfunction "FB_1") (pintype "passive"))
    )
    (net (code "22") (name "Net-(U18-FB)") (class "Default")
      (node (ref "R36") (pin "1") (pinfunction "1_1") (pintype "passive"))
      (node (ref "R37") (pin "1") (pinfunction "1_1") (pintype "passive"))
      (node (ref "U18") (pin "1") (pinfunction "FB_1") (pintype "passive"))
    )
    (net (code "23") (name "Net-(U19-FB)") (class "Default")
      (node (ref "R40") (pin "1") (pinfunction "1_1") (pintype "passive"))
      (node (ref "R41") (pin "1") (pinfunction "1_1") (pintype "passive"))
      (node (ref "U19") (pin "1") (pinfunction "FB_1") (pintype "passive"))
    )
    (net (code "24") (name "VCC1.1") (class "Default")
      (node (ref "C127") (pin "1") (pinfunction "1_1") (pintype "passive"))
      (node (ref "C68") (pin "1") (pinfunction "1_1") (pintype "passive"))
      (node (ref "C69") (pin "1") (pinfunction "1_1") (pintype "passive"))
      (node (ref "C70") (pin "1") (pinfunction "1_1") (pintype "passive"))
      (node (ref "C71") (pin "1") (pinfunction "1_1") (pintype "passive"))
      (node (ref "C72") (pin "1") (pinfunction "1_1") (pintype "passive"))
      (node (ref "C78") (pin "1") (pinfunction "1_1") (pintype "passive"))
      (node (ref "C79") (pin "1") (pinfunction "1_1") (pintype "passive"))
      (node (ref "C80") (pin "1") (pinfunction "1_1") (pintype "passive"))
      (node (ref "C81") (pin "1") (pinfunction "1_1") (pintype "passive"))
      (node (ref "C82") (pin "1") (pinfunction "1_1") (pintype "passive"))
      (node (ref "C88") (pin "1") (pinfunction "1_1") (pintype "passive"))
      (node (ref "C89") (pin "1") (pinfunction "1_1") (pintype "passive"))
      (node (ref "C90") (pin "1") (pinfunction "1_1") (pintype "passive"))
      (node (ref "C91") (pin "1") (pinfunction "1_1") (pintype "passive"))
      (node (ref "C92") (pin "1") (pinfunction "1_1") (pintype "passive"))
      (node (ref "L11") (pin "2") (pinfunction "2_2") (pintype "passive"))
      (node (ref "R40") (pin "2") (pinfunction "2_2") (pintype "passive"))
      (node (ref "U1") (pin "F10") (pinfunction "VDD_MPU_F10") (pintype "power_in"))
      (node (ref "U1") (pin "F11") (pinfunction "VDD_MPU_F11") (pintype "power_in"))
      (node (ref "U1") (pin "F12") (pinfunction "VDD_MPU_F12") (pintype "power_in"))
      (node (ref "U1") (pin "F13") (pinfunction "VDD_MPU_F13") (pintype "power_in"))
      (node (ref "U1") (pin "F6") (pinfunction "VDD_CORE_F6") (pintype "power_in"))
      (node (ref "U1") (pin "F7") (pinfunction "VDD_CORE_F7") (pintype "power_in"))
      (node (ref "U1") (pin "G10") (pinfunction "VDD_CORE_G10") (pintype "power_in"))
      (node (ref "U1") (pin "G13") (pinfunction "VDD_MPU_G13") (pintype "power_in"))
      (node (ref "U1") (pin "G6") (pinfunction "VDD_CORE_G6") (pintype "power_in"))
      (node (ref "U1") (pin "G7") (pinfunction "VDD_CORE_G7") (pintype "power_in"))
      (node (ref "U1") (pin "H11") (pinfunction "VDD_CORE_H11") (pintype "power_in"))
      (node (ref "U1") (pin "H13") (pinfunction "VDD_MPU_H13") (pintype "power_in"))
      (node (ref "U1") (pin "J12") (pinfunction "VDD_CORE_J12") (pintype "power_in"))
      (node (ref "U1") (pin "J13") (pinfunction "VDD_MPU_J13") (pintype "power_in"))
      (node (ref "U1") (pin "K12") (pinfunction "VDD_CORE_K12") (pintype "power_in"))
      (node (ref "U1") (pin "K6") (pinfunction "VDD_CORE_K6") (pintype "power_in"))
      (node (ref "U1") (pin "K8") (pinfunction "VDD_CORE_K8") (pintype "power_in"))
      (node (ref "U1") (pin "L6") (pinfunction "VDD_CORE_L6") (pintype "power_in"))
      (node (ref "U1") (pin "L7") (pinfunction "VDD_CORE_L7") (pintype "power_in"))
      (node (ref "U1") (pin "L8") (pinfunction "VDD_CORE_L8") (pintype "power_in"))
      (node (ref "U1") (pin "L9") (pinfunction "VDD_CORE_L9") (pintype "power_in"))
      (node (ref "U1") (pin "M11") (pinfunction "VDD_CORE_M11") (pintype "power_in"))
      (node (ref "U1") (pin "M13") (pinfunction "VDD_CORE_M13") (pintype "power_in"))
      (node (ref "U1") (pin "N12") (pinfunction "VDD_CORE_N12") (pintype "power_in"))
      (node (ref "U1") (pin "N13") (pinfunction "VDD_CORE_N13") (pintype "power_in"))
      (node (ref "U1") (pin "N8") (pinfunction "VDD_CORE_N8") (pintype "power_in"))
      (node (ref "U1") (pin "N9") (pinfunction "VDD_CORE_N9") (pintype "power_in"))
      (node (ref "U19") (pin "2") (pinfunction "VOUT_2") (pintype "passive"))
    )
    (net (code "25") (name "VCC1.8") (class "Default")
      (node (ref "C108") (pin "1") (pinfunction "1_1") (pintype "passive"))
      (node (ref "C109") (pin "1") (pinfunction "1_1") (pintype "passive"))
      (node (ref "C110") (pin "1") (pinfunction "1_1") (pintype "passive"))
      (node (ref "C111") (pin "1") (pinfunction "1_1") (pintype "passive"))
      (node (ref "C112") (pin "1") (pinfunction "1_1") (pintype "passive"))
      (node (ref "C143") (pin "1") (pinfunction "1_1") (pintype "passive"))
      (node (ref "C144") (pin "1") (pinfunction "1_1") (pintype "passive"))
      (node (ref "C48") (pin "1") (pinfunction "1_1") (pintype "passive"))
      (node (ref "C93") (pin "1") (pinfunction "1_1") (pintype "passive"))
      (node (ref "C94") (pin "1") (pinfunction "1_1") (pintype "passive"))
      (node (ref "C95") (pin "1") (pinfunction "1_1") (pintype "passive"))
      (node (ref "C96") (pin "1") (pinfunction "1_1") (pintype "passive"))
      (node (ref "C97") (pin "1") (pinfunction "1_1") (pintype "passive"))
      (node (ref "L4") (pin "2") (pinfunction "2_2") (pintype "passive"))
      (node (ref "L5") (pin "1") (pinfunction "1_1") (pintype "passive"))
      (node (ref "L7") (pin "1") (pinfunction "1_1") (pintype "passive"))
      (node (ref "R28") (pin "2") (pinfunction "2_2") (pintype "passive"))
      (node (ref "U1") (pin "D10") (pinfunction "VDDS_SRAM_MPU_BB_D10") (pintype "power_in"))
      (node (ref "U1") (pin "E14") (pinfunction "VDDS_E14") (pintype "power_in"))
      (node (ref "U1") (pin "E6") (pinfunction "VDDS_E6") (pintype "power_in"))
      (node (ref "U1") (pin "E7") (pinfunction "VDDS_PLL_DDR_E7") (pintype "power_in"))
      (node (ref "U1") (pin "E9") (pinfunction "VDDS_SRAM_CORE_BG_E9") (pintype "power_in"))
      (node (ref "U1") (pin "F9") (pinfunction "VDDS_F9") (pintype "power_in"))
      (node (ref "U1") (pin "K13") (pinfunction "VDDS_K13") (pintype "power_in"))
      (node (ref "U1") (pin "N16") (pinfunction "VDDA1P8V_USB0_N16") (pintype "power_in"))
      (node (ref "U1") (pin "N6") (pinfunction "VDDS_N6") (pintype "power_in"))
      (node (ref "U1") (pin "P14") (pinfunction "VDDS_P14") (pintype "power_in"))
      (node (ref "U1") (pin "P9") (pinfunction "VDDS_P9") (pintype "power_in"))
      (node (ref "U1") (pin "R10") (pinfunction "VDDS_PLL_CORE_LCD_R10") (pintype "power_in"))
      (node (ref "U1") (pin "R11") (pinfunction "VDDS_OSC_R11") (pintype "power_in"))
      (node (ref "U1") (pin "R16") (pinfunction "VDDA1P8V_USB1_R16") (pintype "power_in"))
      (node (ref "U11") (pin "2") (pinfunction "VOUT_2") (pintype "passive"))
    )
    (net (code "26") (name "VCC3") (class "Default")
      (node (ref "C60") (pin "1") (pinfunction "1_1") (pintype "passive"))
      (node (ref "C63") (pin "1") (pinfunction "1_1") (pintype "passive"))
      (node (ref "C64") (pin "1") (pinfunction "1_1") (pintype "passive"))
      (node (ref "C65") (pin "1") (pinfunction "1_1") (pintype "passive"))
      (node (ref "C66") (pin "1") (pinfunction "1_1") (pintype "passive"))
      (node (ref "C67") (pin "1") (pinfunction "1_1") (pintype "passive"))
      (node (ref "C73") (pin "1") (pinfunction "1_1") (pintype "passive"))
      (node (ref "C74") (pin "1") (pinfunction "1_1") (pintype "passive"))
      (node (ref "C75") (pin "1") (pinfunction "1_1") (pintype "passive"))
      (node (ref "C76") (pin "1") (pinfunction "1_1") (pintype "passive"))
      (node (ref "C77") (pin "1") (pinfunction "1_1") (pintype "passive"))
      (node (ref "C83") (pin "1") (pinfunction "1_1") (pintype "passive"))
      (node (ref "C84") (pin "1") (pinfunction "1_1") (pintype "passive"))
      (node (ref "C85") (pin "1") (pinfunction "1_1") (pintype "passive"))
      (node (ref "C86") (pin "1") (pinfunction "1_1") (pintype "passive"))
      (node (ref "C87") (pin "1") (pinfunction "1_1") (pintype "passive"))
      (node (ref "L10") (pin "2") (pinfunction "2_2") (pintype "passive"))
      (node (ref "R36") (pin "2") (pinfunction "2_2") (pintype "passive"))
      (node (ref "R42") (pin "1") (pinfunction "1_1") (pintype "passive"))
      (node (ref "U1") (pin "E10") (pinfunction "VDDSHV6_E10") (pintype "power_in"))
      (node (ref "U1") (pin "E11") (pinfunction "VDDSHV6_E11") (pintype "power_in"))
      (node (ref "U1") (pin "E12") (pinfunction "VDDSHV6_E12") (pintype "power_in"))
      (node (ref "U1") (pin "E13") (pinfunction "VDDSHV6_E13") (pintype "power_in"))
      (node (ref "U1") (pin "F14") (pinfunction "VDDSHV6_F14") (pintype "power_in"))
      (node (ref "U1") (pin "G14") (pinfunction "VDDSHV6_G14") (pintype "power_in"))
      (node (ref "U1") (pin "H14") (pinfunction "VDDSHV4_H14") (pintype "power_in"))
      (node (ref "U1") (pin "J14") (pinfunction "VDDSHV4_J14") (pintype "power_in"))
      (node (ref "U1") (pin "K14") (pinfunction "VDDSHV5_K14") (pintype "power_in"))
      (node (ref "U1") (pin "L14") (pinfunction "VDDSHV5_L14") (pintype "power_in"))
      (node (ref "U1") (pin "N15") (pinfunction "VDDA3P3V_USB0_N15") (pintype "power_in"))
      (node (ref "U1") (pin "N5") (pinfunction "VDDSHV6_N5") (pintype "power_in"))
      (node (ref "U1") (pin "P10") (pinfunction "VDDSHV2_P10") (pintype "power_in"))
      (node (ref "U1") (pin "P11") (pinfunction "VDDSHV2_P11") (pintype "power_in"))
      (node (ref "U1") (pin "P12") (pinfunction "VDDSHV3_P12") (pintype "power_in"))
      (node (ref "U1") (pin "P13") (pinfunction "VDDSHV3_P13") (pintype "power_in"))
      (node (ref "U1") (pin "P5") (pinfunction "VDDSHV6_P5") (pintype "power_in"))
      (node (ref "U1") (pin "P6") (pinfunction "VDDSHV6_P6") (pintype "power_in"))
      (node (ref "U1") (pin "P7") (pinfunction "VDDSHV1_P7") (pintype "power_in"))
      (node (ref "U1") (pin "P8") (pinfunction "VDDSHV1_P8") (pintype "power_in"))
      (node (ref "U1") (pin "R15") (pinfunction "VDDA3P3V_USB1_R15") (pintype "power_in"))
      (node (ref "U18") (pin "2") (pinfunction "VOUT_2") (pintype "passive"))
    )
    (net (code "27") (name "VCCADC") (class "Default")
      (node (ref "C106") (pin "1") (pinfunction "1_1") (pintype "passive"))
      (node (ref "L5") (pin "2") (pinfunction "2_2") (pintype "passive"))
      (node (ref "U1") (pin "D8") (pinfunction "VDDA_ADC_D8") (pintype "power_in"))
    )
    (net (code "28") (name "VCCM") (class "Default")
      (node (ref "C100") (pin "1") (pinfunction "1_1") (pintype "passive"))
      (node (ref "C101") (pin "1") (pinfunction "1_1") (pintype "passive"))
      (node (ref "C102") (pin "1") (pinfunction "1_1") (pintype "passive"))
      (node (ref "C98") (pin "1") (pinfunction "1_1") (pintype "passive"))
      (node (ref "C99") (pin "1") (pinfunction "1_1") (pintype "passive"))
      (node (ref "U1") (pin "E5") (pinfunction "VDDS_DDR_E5") (pintype "power_in"))
      (node (ref "U1") (pin "F5") (pinfunction "VDDS_DDR_F5") (pintype "power_in"))
      (node (ref "U1") (pin "G5") (pinfunction "VDDS_DDR_G5") (pintype "power_in"))
      (node (ref "U1") (pin "H5") (pinfunction "VDDS_DDR_H5") (pintype "power_in"))
      (node (ref "U1") (pin "J5") (pinfunction "VDDS_DDR_J5") (pintype "power_in"))
      (node (ref "U1") (pin "K5") (pinfunction "VDDS_DDR_K5") (pintype "power_in"))
      (node (ref "U1") (pin "L5") (pinfunction "VDDS_DDR_L5") (pintype "power_in"))
    )
    (net (code "29") (name "VDDS") (class "Default")
      (node (ref "C114") (pin "1") (pinfunction "1_1") (pintype "passive"))
      (node (ref "U1") (pin "D7") (pinfunction "VDDS_RTC_D7") (pintype "power_in"))
      (node (ref "VR1") (pin "4") (pinfunction "VOUT_4") (pintype "passive"))
    )
    (net (code "30") (name "VSYS") (class "Default")
      (node (ref "C113") (pin "1") (pinfunction "1_1") (pintype "passive"))
      (node (ref "C126") (pin "1") (pinfunction "1_1") (pintype "passive"))
      (node (ref "C47") (pin "1") (pinfunction "1_1") (pintype "passive"))
      (node (ref "C59") (pin "1") (pinfunction "1_1") (pintype "passive"))
      (node (ref "R31") (pin "1") (pinfunction "1_1") (pintype "passive"))
      (node (ref "R38") (pin "1") (pinfunction "1_1") (pintype "passive"))
      (node (ref "U11") (pin "7") (pinfunction "PVIN_7") (pintype "power_in"))
      (node (ref "U11") (pin "8") (pinfunction "PVIN_8") (pintype "power_in"))
      (node (ref "U11") (pin "9") (pinfunction "VCC_9") (pintype "power_in"))
      (node (ref "U18") (pin "7") (pinfunction "PVIN_7") (pintype "power_in"))
      (node (ref "U18") (pin "8") (pinfunction "PVIN_8") (pintype "power_in"))
      (node (ref "U18") (pin "9") (pinfunction "VCC_9") (pintype "power_in"))
      (node (ref "U19") (pin "7") (pinfunction "PVIN_7") (pintype "power_in"))
      (node (ref "U19") (pin "8") (pinfunction "PVIN_8") (pintype "power_in"))
      (node (ref "U19") (pin "9") (pinfunction "VCC_9") (pintype "power_in"))
      (node (ref "VR1") (pin "1") (pinfunction "STBY_1") (pintype "passive"))
      (node (ref "VR1") (pin "3") (pinfunction "VIN_3") (pintype "passive"))
    )
    (net (code "31") (name "unconnected-(U1D-VDD_MPU_MON-PadA2)") (class "Default")
      (node (ref "U1") (pin "A2") (pinfunction "VDD_MPU_MON_A2") (pintype "passive"))
    )
    (net (code "32") (name "unconnected-(VR1-SEL-Pad5)") (class "Default")
      (node (ref "VR1") (pin "5") (pinfunction "SEL_5") (pintype "passive"))
    )
  )
)
